# SCH_single-layer-routed_2024-06-21.net
KiCad netlist of a schematic drawn in EasyEDA
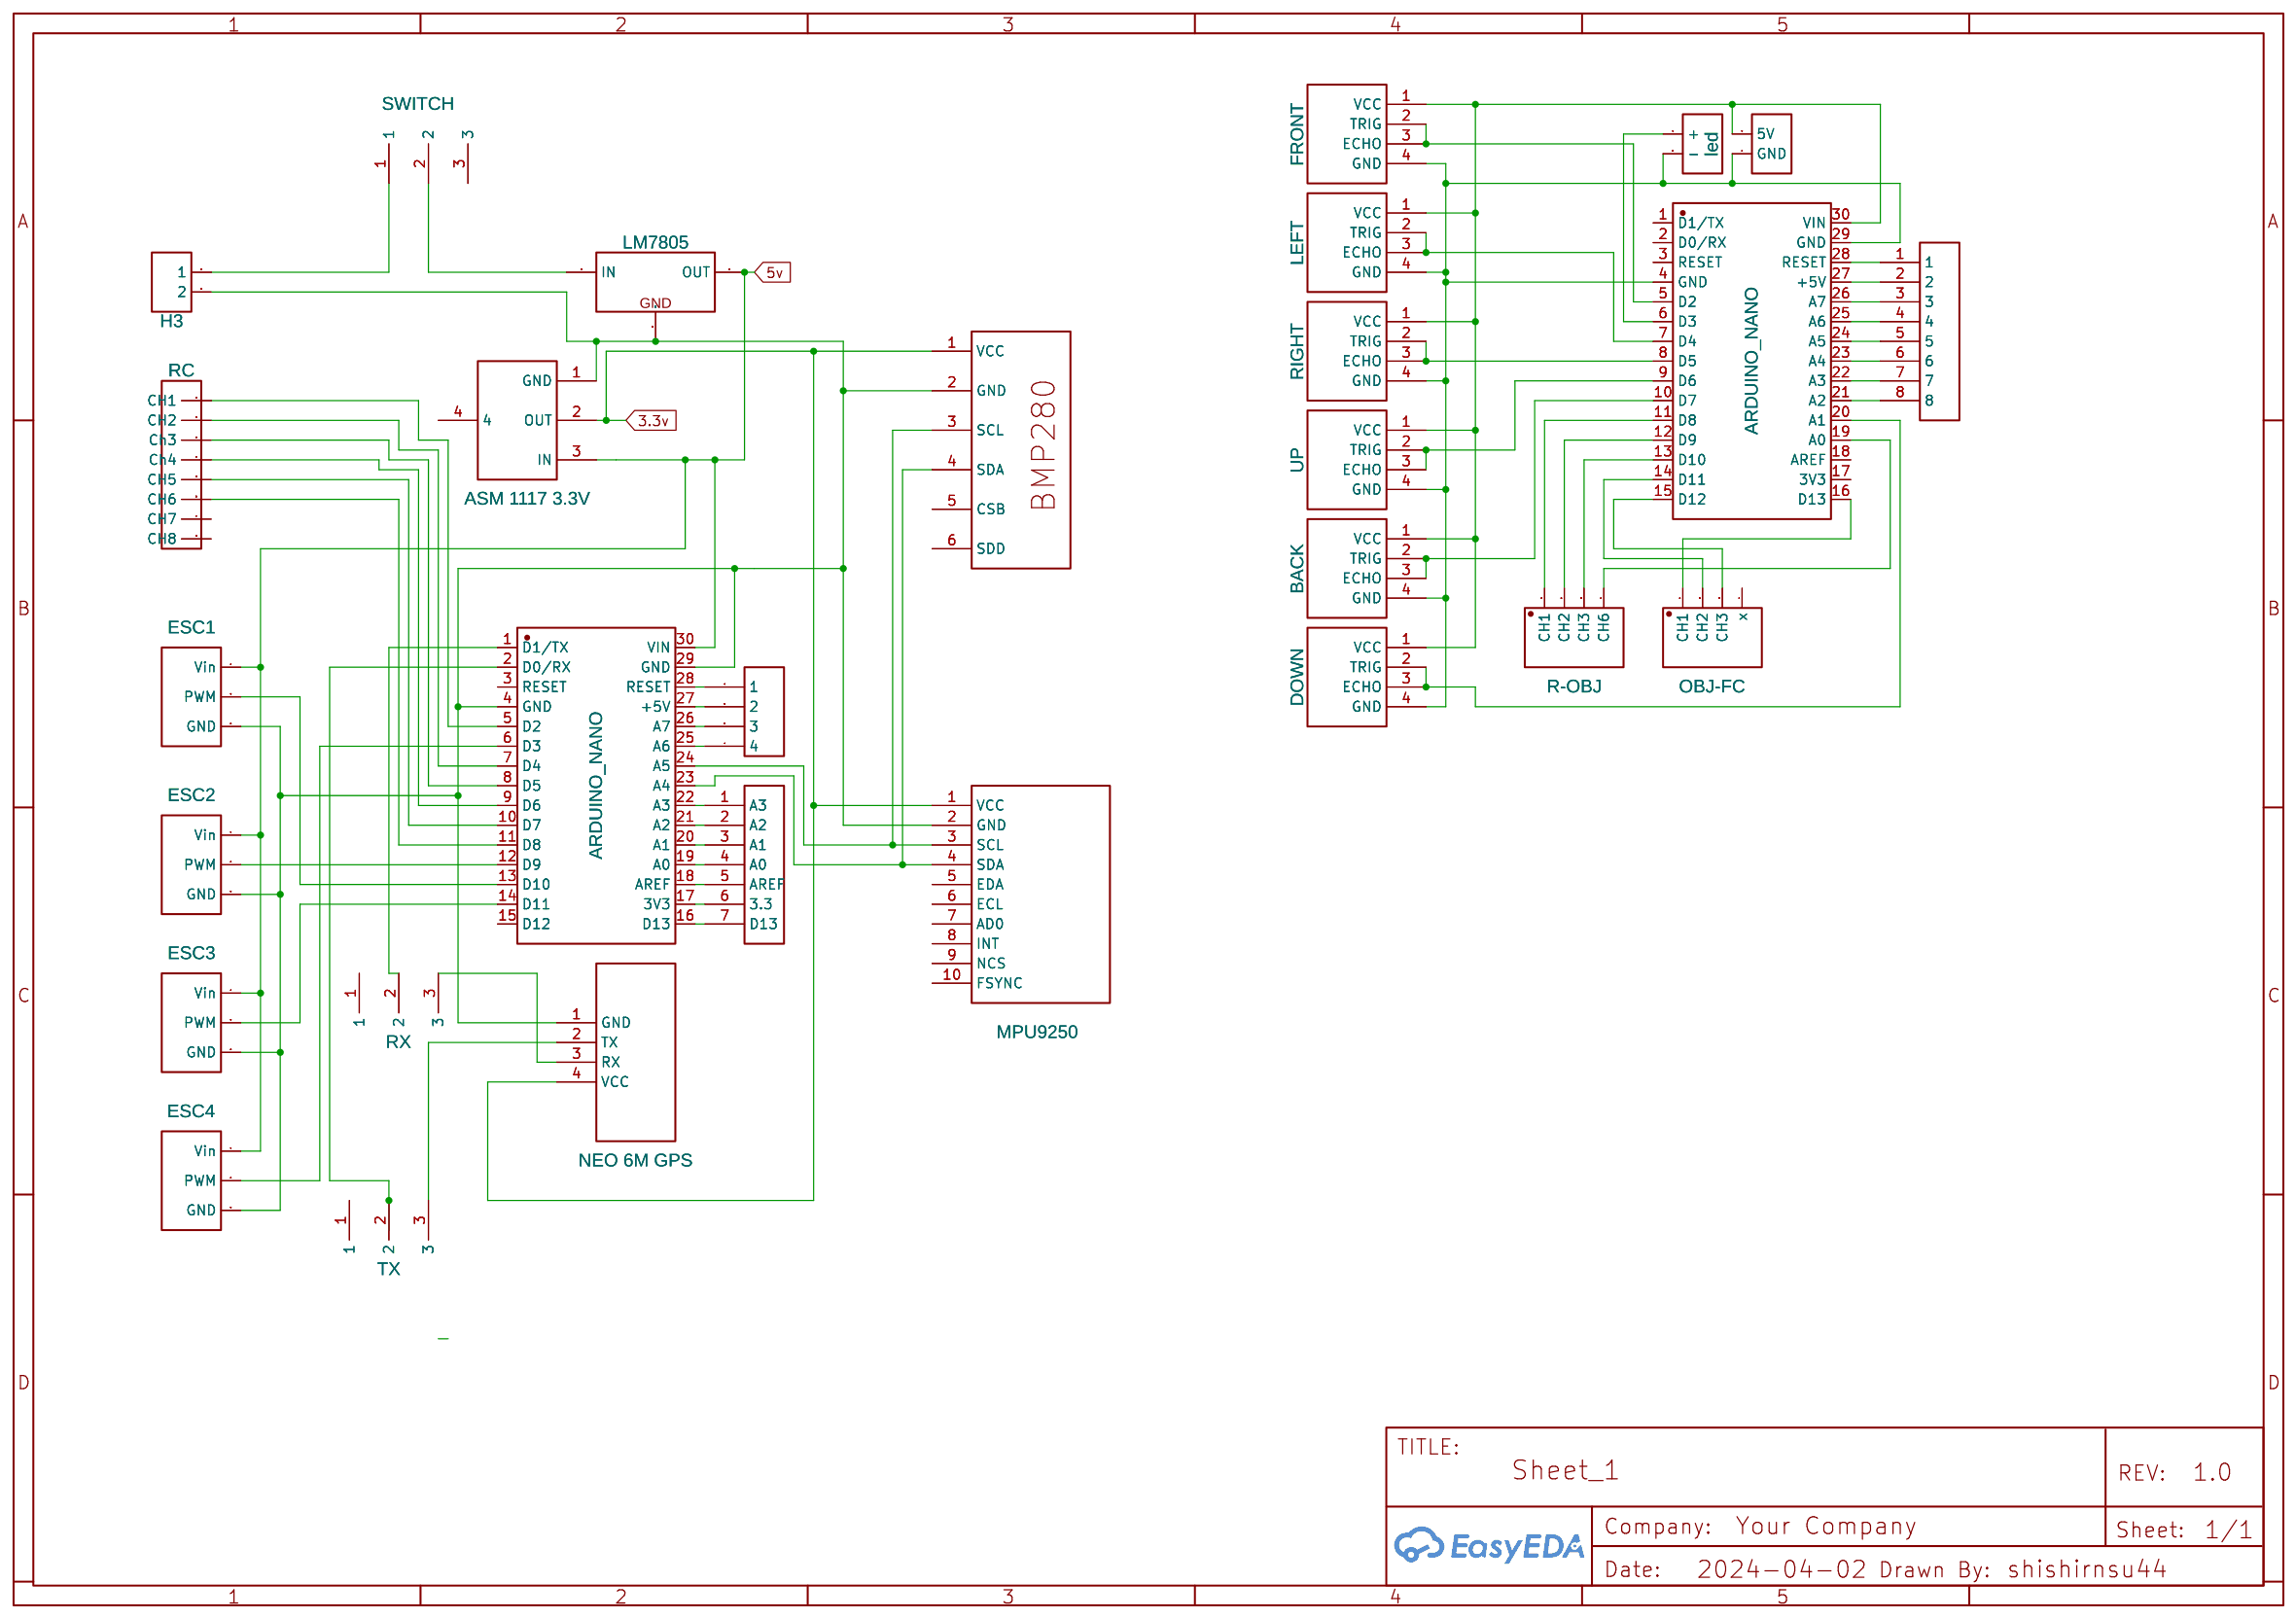
[diagram p0: schematic sheet]

(export (version "E")
  (design (tool "Eeschema 10.0.6"))
  (components
    (comp (ref "BACK")
      (value "BORNERA SENSOR ULTRASONICO HC-SR04")
      (libsource (lib "") (part "BORNERA SENSOR ULTRASONICO HC-SR04"))
    )
    (comp (ref "DOWN") (value "Down") (libsource (lib "") (part "BORNERA SENSOR ULTRASONICO HC-SR04_5")))
    (comp (ref "ESC1") (value "ESC") (libsource (lib "") (part "ESC")))
    (comp (ref "ESC2") (value "ESC") (libsource (lib "") (part "ESC")))
    (comp (ref "ESC3") (value "ESC") (libsource (lib "") (part "ESC")))
    (comp (ref "ESC4") (value "ESC") (libsource (lib "") (part "ESC")))
    (comp (ref "FRONT") (value "Front") (libsource (lib "") (part "BORNERA SENSOR ULTRASONICO HC-SR04_2")))
    (comp (ref "H1")
      (value "1x2_Male_Pin_Header")
      (fields (field (name "Manufacturer Part") "210S-1*8P L=11.6MMGold-plated black"))
      (libsource (lib "") (part "1x2_Male_Pin_Header_2"))
    )
    (comp (ref "H2")
      (value "led")
      (fields (field (name "Manufacturer Part") "210S-1*8P L=11.6MMGold-plated black"))
      (libsource (lib "") (part "1x2_Male_Pin_Header"))
    )
    (comp (ref "H3")
      (value "1x2_Male_Pin_Header")
      (fields (field (name "Manufacturer Part") "210S-1*8P L=11.6MMGold-plated black"))
      (libsource (lib "") (part "1x2_Male_Pin_Header_1"))
    )
    (comp (ref "LEFT") (value "Left") (libsource (lib "") (part "BORNERA SENSOR ULTRASONICO HC-SR04_4")))
    (comp (ref "MODULE2")
      (value "NEO 6M GPS")
      (libsource (lib "") (part "UBLOX NEO 6M GPS MODULE NO-ANTENNA"))
    )
    (comp (ref "OBJ-FC")
      (value "Header-Male-2.54_1x4")
      (fields (field (name "Manufacturer Part") "B-2100S04P-A110") (field (name "Manufacturer") "Ckmtw(灿科盟)"))
      (libsource (lib "") (part "Header-Male-2.54_1x4_1"))
    )
    (comp (ref "P2")
      (value "HEADER4x1")
      (fields (field (name "Manufacturer Part") "New SchematicLib"))
      (libsource (lib "") (part "HEADER4x1"))
    )
    (comp (ref "R-OBJ")
      (value "Header-Male-2.54_1x4")
      (fields (field (name "Manufacturer Part") "B-2100S04P-A110") (field (name "Manufacturer") "Ckmtw(灿科盟)"))
      (libsource (lib "") (part "Header-Male-2.54_1x4"))
    )
    (comp (ref "RC")
      (value "pinheader08x1")
      (fields (field (name "Manufacturer Part") "Header 6x1"))
      (libsource (lib "") (part "pinheader08x1"))
    )
    (comp (ref "RIGHT") (value "Rignt") (libsource (lib "") (part "BORNERA SENSOR ULTRASONICO HC-SR04_3")))
    (comp (ref "RX") (value "SlideSwitch") (libsource (lib "") (part "SlideSwitch_2")))
    (comp (ref "SWITCH") (value "SlideSwitch") (libsource (lib "") (part "SlideSwitch")))
    (comp (ref "TX") (value "SlideSwitch") (libsource (lib "") (part "SlideSwitch_1")))
    (comp (ref "U1") (value "ARDUINO_NANO") (libsource (lib "") (part "ARDUINO_NANO")))
    (comp (ref "U2")
      (value "BMP280 Pressure/Temp/Altitudesensor")
      (libsource (lib "") (part "BMP280 Pressure/Temp/Altitudesensor"))
    )
    (comp (ref "U3") (value "MPU9250") (libsource (lib "") (part "GY9250(MPU9250)")))
    (comp (ref "U4")
      (value "LM7805")
      (fields (field (name "Manufacturer") "TF"))
      (libsource (lib "") (part "LM7805"))
    )
    (comp (ref "U5") (value "ASM 1117 3.3V") (libsource (lib "") (part "ASM 1117 5.0V")))
    (comp (ref "U6") (value "ARDUINO_NANO") (libsource (lib "") (part "ARDUINO_NANO")))
    (comp (ref "U7") (value "header8x1") (libsource (lib "") (part "header8x1")))
    (comp (ref "U9") (value "header7X1") (libsource (lib "") (part "header7X1")))
    (comp (ref "UP")
      (value "BORNERA SENSOR ULTRASONICO HC-SR04")
      (libsource (lib "") (part "BORNERA SENSOR ULTRASONICO HC-SR04_1"))
    )
  )
  (nets
    (net (code "1") (name "3.3v") (class "Default")
      (node (ref "MODULE2") (pin "4") (pinfunction "VCC_4") (pintype "unspecified"))
      (node (ref "U2") (pin "1") (pinfunction "VCC_1") (pintype "unspecified"))
      (node (ref "U3") (pin "1") (pinfunction "VCC_1") (pintype "unspecified"))
      (node (ref "U5") (pin "2") (pinfunction "OUT_2") (pintype "unspecified"))
    )
    (net (code "2") (name "5v") (class "Default")
      (node (ref "ESC1") (pin "1") (pinfunction "Vin_1") (pintype "input"))
      (node (ref "ESC2") (pin "1") (pinfunction "Vin_1") (pintype "input"))
      (node (ref "ESC3") (pin "1") (pinfunction "Vin_1") (pintype "input"))
      (node (ref "ESC4") (pin "1") (pinfunction "Vin_1") (pintype "input"))
      (node (ref "U1") (pin "30") (pinfunction "VIN_30") (pintype "unspecified"))
      (node (ref "U4") (pin "3") (pinfunction "OUT_3") (pintype "unspecified"))
      (node (ref "U5") (pin "3") (pinfunction "IN_3") (pintype "unspecified"))
    )
    (net (code "3") (name "Net-(BACK-ECHO)") (class "Default")
      (node (ref "BACK") (pin "2") (pinfunction "TRIG_2") (pintype "unspecified"))
      (node (ref "BACK") (pin "3") (pinfunction "ECHO_3") (pintype "unspecified"))
      (node (ref "U6") (pin "10") (pinfunction "D7_10") (pintype "unspecified"))
    )
    (net (code "4") (name "Net-(BACK-GND)") (class "Default")
      (node (ref "BACK") (pin "4") (pinfunction "GND_4") (pintype "unspecified"))
      (node (ref "DOWN") (pin "4") (pinfunction "GND_4") (pintype "unspecified"))
      (node (ref "FRONT") (pin "4") (pinfunction "GND_4") (pintype "unspecified"))
      (node (ref "H1") (pin "1") (pinfunction "GND_1") (pintype "unspecified"))
      (node (ref "H2") (pin "2") (pinfunction "-_2") (pintype "unspecified"))
      (node (ref "LEFT") (pin "4") (pinfunction "GND_4") (pintype "unspecified"))
      (node (ref "RIGHT") (pin "4") (pinfunction "GND_4") (pintype "unspecified"))
      (node (ref "U6") (pin "29") (pinfunction "GND_29") (pintype "unspecified"))
      (node (ref "U6") (pin "4") (pinfunction "GND_4") (pintype "unspecified"))
      (node (ref "UP") (pin "4") (pinfunction "GND_4") (pintype "unspecified"))
    )
    (net (code "5") (name "Net-(BACK-VCC)") (class "Default")
      (node (ref "BACK") (pin "1") (pinfunction "VCC_1") (pintype "unspecified"))
      (node (ref "DOWN") (pin "1") (pinfunction "VCC_1") (pintype "unspecified"))
      (node (ref "FRONT") (pin "1") (pinfunction "VCC_1") (pintype "unspecified"))
      (node (ref "H1") (pin "2") (pinfunction "5V_2") (pintype "unspecified"))
      (node (ref "LEFT") (pin "1") (pinfunction "VCC_1") (pintype "unspecified"))
      (node (ref "RIGHT") (pin "1") (pinfunction "VCC_1") (pintype "unspecified"))
      (node (ref "U6") (pin "30") (pinfunction "VIN_30") (pintype "unspecified"))
      (node (ref "UP") (pin "1") (pinfunction "VCC_1") (pintype "unspecified"))
    )
    (net (code "6") (name "Net-(DOWN-ECHO)") (class "Default")
      (node (ref "DOWN") (pin "2") (pinfunction "TRIG_2") (pintype "unspecified"))
      (node (ref "DOWN") (pin "3") (pinfunction "ECHO_3") (pintype "unspecified"))
      (node (ref "U6") (pin "20") (pinfunction "A1_20") (pintype "unspecified"))
    )
    (net (code "7") (name "Net-(ESC1-GND)") (class "Default")
      (node (ref "ESC1") (pin "3") (pinfunction "GND_3") (pintype "input"))
      (node (ref "ESC2") (pin "3") (pinfunction "GND_3") (pintype "input"))
      (node (ref "ESC3") (pin "3") (pinfunction "GND_3") (pintype "input"))
      (node (ref "ESC4") (pin "3") (pinfunction "GND_3") (pintype "input"))
      (node (ref "H3") (pin "2") (pinfunction "2_2") (pintype "unspecified"))
      (node (ref "MODULE2") (pin "1") (pinfunction "GND_1") (pintype "unspecified"))
      (node (ref "U1") (pin "29") (pinfunction "GND_29") (pintype "unspecified"))
      (node (ref "U1") (pin "4") (pinfunction "GND_4") (pintype "unspecified"))
      (node (ref "U2") (pin "2") (pinfunction "GND_2") (pintype "unspecified"))
      (node (ref "U3") (pin "2") (pinfunction "GND_2") (pintype "unspecified"))
      (node (ref "U4") (pin "2") (pinfunction "GND_2") (pintype "unspecified"))
      (node (ref "U5") (pin "1") (pinfunction "GND_1") (pintype "unspecified"))
    )
    (net (code "8") (name "Net-(ESC1-PWM)") (class "Default")
      (node (ref "ESC1") (pin "2") (pinfunction "PWM_2") (pintype "input"))
      (node (ref "U1") (pin "13") (pinfunction "D10_13") (pintype "unspecified"))
    )
    (net (code "9") (name "Net-(ESC2-PWM)") (class "Default")
      (node (ref "ESC2") (pin "2") (pinfunction "PWM_2") (pintype "input"))
      (node (ref "U1") (pin "12") (pinfunction "D9_12") (pintype "unspecified"))
    )
    (net (code "10") (name "Net-(ESC3-PWM)") (class "Default")
      (node (ref "ESC3") (pin "2") (pinfunction "PWM_2") (pintype "input"))
      (node (ref "U1") (pin "14") (pinfunction "D11_14") (pintype "unspecified"))
    )
    (net (code "11") (name "Net-(ESC4-PWM)") (class "Default")
      (node (ref "ESC4") (pin "2") (pinfunction "PWM_2") (pintype "input"))
      (node (ref "U1") (pin "6") (pinfunction "D3_6") (pintype "unspecified"))
    )
    (net (code "12") (name "Net-(FRONT-ECHO)") (class "Default")
      (node (ref "FRONT") (pin "2") (pinfunction "TRIG_2") (pintype "unspecified"))
      (node (ref "FRONT") (pin "3") (pinfunction "ECHO_3") (pintype "unspecified"))
      (node (ref "U6") (pin "5") (pinfunction "D2_5") (pintype "unspecified"))
    )
    (net (code "13") (name "Net-(H2-+)") (class "Default")
      (node (ref "H2") (pin "1") (pinfunction "+_1") (pintype "unspecified"))
      (node (ref "U6") (pin "6") (pinfunction "D3_6") (pintype "unspecified"))
    )
    (net (code "14") (name "Net-(H3-Pad1)") (class "Default")
      (node (ref "H3") (pin "1") (pinfunction "1_1") (pintype "unspecified"))
      (node (ref "SWITCH") (pin "1") (pinfunction "1_1") (pintype "unspecified"))
    )
    (net (code "15") (name "Net-(LEFT-ECHO)") (class "Default")
      (node (ref "LEFT") (pin "2") (pinfunction "TRIG_2") (pintype "unspecified"))
      (node (ref "LEFT") (pin "3") (pinfunction "ECHO_3") (pintype "unspecified"))
      (node (ref "U6") (pin "7") (pinfunction "D4_7") (pintype "unspecified"))
    )
    (net (code "16") (name "Net-(MODULE2-RX)") (class "Default")
      (node (ref "MODULE2") (pin "3") (pinfunction "RX_3") (pintype "unspecified"))
      (node (ref "RX") (pin "3") (pinfunction "3_3") (pintype "unspecified"))
    )
    (net (code "17") (name "Net-(MODULE2-TX)") (class "Default")
      (node (ref "MODULE2") (pin "2") (pinfunction "TX_2") (pintype "unspecified"))
      (node (ref "TX") (pin "3") (pinfunction "3_3") (pintype "unspecified"))
    )
    (net (code "18") (name "Net-(OBJ-FC-CH1)") (class "Default")
      (node (ref "OBJ-FC") (pin "1") (pinfunction "CH1_1") (pintype "unspecified"))
      (node (ref "U6") (pin "16") (pinfunction "D13_16") (pintype "unspecified"))
    )
    (net (code "19") (name "Net-(OBJ-FC-CH2)") (class "Default")
      (node (ref "OBJ-FC") (pin "2") (pinfunction "CH2_2") (pintype "unspecified"))
      (node (ref "U6") (pin "14") (pinfunction "D11_14") (pintype "unspecified"))
    )
    (net (code "20") (name "Net-(OBJ-FC-CH3)") (class "Default")
      (node (ref "OBJ-FC") (pin "3") (pinfunction "CH3_3") (pintype "unspecified"))
      (node (ref "U6") (pin "15") (pinfunction "D12_15") (pintype "unspecified"))
    )
    (net (code "21") (name "Net-(P2-Pad1)") (class "Default")
      (node (ref "P2") (pin "1") (pinfunction "1_1") (pintype "input"))
      (node (ref "U1") (pin "28") (pinfunction "RESET_28") (pintype "unspecified"))
    )
    (net (code "22") (name "Net-(R-OBJ-CH1)") (class "Default")
      (node (ref "R-OBJ") (pin "1") (pinfunction "CH1_1") (pintype "unspecified"))
      (node (ref "U6") (pin "11") (pinfunction "D8_11") (pintype "unspecified"))
    )
    (net (code "23") (name "Net-(R-OBJ-CH2)") (class "Default")
      (node (ref "R-OBJ") (pin "2") (pinfunction "CH2_2") (pintype "unspecified"))
      (node (ref "U6") (pin "12") (pinfunction "D9_12") (pintype "unspecified"))
    )
    (net (code "24") (name "Net-(R-OBJ-CH3)") (class "Default")
      (node (ref "R-OBJ") (pin "3") (pinfunction "CH3_3") (pintype "unspecified"))
      (node (ref "U6") (pin "13") (pinfunction "D10_13") (pintype "unspecified"))
    )
    (net (code "25") (name "Net-(R-OBJ-CH6)") (class "Default")
      (node (ref "R-OBJ") (pin "4") (pinfunction "CH6_4") (pintype "unspecified"))
      (node (ref "U6") (pin "19") (pinfunction "A0_19") (pintype "unspecified"))
    )
    (net (code "26") (name "Net-(RC-CH1)") (class "Default")
      (node (ref "RC") (pin "1") (pinfunction "CH1_1") (pintype "unspecified"))
      (node (ref "U1") (pin "5") (pinfunction "D2_5") (pintype "unspecified"))
    )
    (net (code "27") (name "Net-(RC-CH2)") (class "Default")
      (node (ref "RC") (pin "2") (pinfunction "CH2_2") (pintype "unspecified"))
      (node (ref "U1") (pin "7") (pinfunction "D4_7") (pintype "unspecified"))
    )
    (net (code "28") (name "Net-(RC-CH5)") (class "Default")
      (node (ref "RC") (pin "5") (pinfunction "CH5_5") (pintype "unspecified"))
      (node (ref "U1") (pin "10") (pinfunction "D7_10") (pintype "unspecified"))
    )
    (net (code "29") (name "Net-(RC-CH6)") (class "Default")
      (node (ref "RC") (pin "6") (pinfunction "CH6_6") (pintype "unspecified"))
      (node (ref "U1") (pin "11") (pinfunction "D8_11") (pintype "unspecified"))
    )
    (net (code "30") (name "Net-(RC-Ch3)") (class "Default")
      (node (ref "RC") (pin "3") (pinfunction "Ch3_3") (pintype "unspecified"))
      (node (ref "U1") (pin "8") (pinfunction "D5_8") (pintype "unspecified"))
    )
    (net (code "31") (name "Net-(RC-Ch4)") (class "Default")
      (node (ref "RC") (pin "4") (pinfunction "Ch4_4") (pintype "unspecified"))
      (node (ref "U1") (pin "9") (pinfunction "D6_9") (pintype "unspecified"))
    )
    (net (code "32") (name "Net-(RIGHT-ECHO)") (class "Default")
      (node (ref "RIGHT") (pin "2") (pinfunction "TRIG_2") (pintype "unspecified"))
      (node (ref "RIGHT") (pin "3") (pinfunction "ECHO_3") (pintype "unspecified"))
      (node (ref "U6") (pin "8") (pinfunction "D5_8") (pintype "unspecified"))
    )
    (net (code "33") (name "Net-(U1-+5V)") (class "Default")
      (node (ref "P2") (pin "2") (pinfunction "2_2") (pintype "input"))
      (node (ref "U1") (pin "27") (pinfunction "+5V_27") (pintype "unspecified"))
    )
    (net (code "34") (name "Net-(U1-3V3)") (class "Default")
      (node (ref "U1") (pin "17") (pinfunction "3V3_17") (pintype "unspecified"))
      (node (ref "U9") (pin "6") (pinfunction "3.3_6") (pintype "unspecified"))
    )
    (net (code "35") (name "Net-(U1-A0)") (class "Default")
      (node (ref "U1") (pin "19") (pinfunction "A0_19") (pintype "unspecified"))
      (node (ref "U9") (pin "4") (pinfunction "A0_4") (pintype "unspecified"))
    )
    (net (code "36") (name "Net-(U1-A1)") (class "Default")
      (node (ref "U1") (pin "20") (pinfunction "A1_20") (pintype "unspecified"))
      (node (ref "U9") (pin "3") (pinfunction "A1_3") (pintype "unspecified"))
    )
    (net (code "37") (name "Net-(U1-A2)") (class "Default")
      (node (ref "U1") (pin "21") (pinfunction "A2_21") (pintype "unspecified"))
      (node (ref "U9") (pin "2") (pinfunction "A2_2") (pintype "unspecified"))
    )
    (net (code "38") (name "Net-(U1-A3)") (class "Default")
      (node (ref "U1") (pin "22") (pinfunction "A3_22") (pintype "unspecified"))
      (node (ref "U9") (pin "1") (pinfunction "A3_1") (pintype "unspecified"))
    )
    (net (code "39") (name "Net-(U1-A4)") (class "Default")
      (node (ref "U1") (pin "23") (pinfunction "A4_23") (pintype "unspecified"))
      (node (ref "U2") (pin "4") (pinfunction "SDA_4") (pintype "unspecified"))
      (node (ref "U3") (pin "4") (pinfunction "SDA_4") (pintype "unspecified"))
    )
    (net (code "40") (name "Net-(U1-A5)") (class "Default")
      (node (ref "U1") (pin "24") (pinfunction "A5_24") (pintype "unspecified"))
      (node (ref "U2") (pin "3") (pinfunction "SCL_3") (pintype "unspecified"))
      (node (ref "U3") (pin "3") (pinfunction "SCL_3") (pintype "unspecified"))
    )
    (net (code "41") (name "Net-(U1-A6)") (class "Default")
      (node (ref "P2") (pin "4") (pinfunction "4_4") (pintype "input"))
      (node (ref "U1") (pin "25") (pinfunction "A6_25") (pintype "unspecified"))
    )
    (net (code "42") (name "Net-(U1-A7)") (class "Default")
      (node (ref "P2") (pin "3") (pinfunction "3_3") (pintype "input"))
      (node (ref "U1") (pin "26") (pinfunction "A7_26") (pintype "unspecified"))
    )
    (net (code "43") (name "Net-(U1-AREF)") (class "Default")
      (node (ref "U1") (pin "18") (pinfunction "AREF_18") (pintype "unspecified"))
      (node (ref "U9") (pin "5") (pinfunction "AREF_5") (pintype "unspecified"))
    )
    (net (code "44") (name "Net-(U1-D0{slash}RX)") (class "Default")
      (node (ref "TX") (pin "2") (pinfunction "2_2") (pintype "unspecified"))
      (node (ref "U1") (pin "2") (pinfunction "D0/RX_2") (pintype "unspecified"))
    )
    (net (code "45") (name "Net-(U1-D1{slash}TX)") (class "Default")
      (node (ref "RX") (pin "2") (pinfunction "2_2") (pintype "unspecified"))
      (node (ref "U1") (pin "1") (pinfunction "D1/TX_1") (pintype "unspecified"))
    )
    (net (code "46") (name "Net-(U1-D13)") (class "Default")
      (node (ref "U1") (pin "16") (pinfunction "D13_16") (pintype "unspecified"))
      (node (ref "U9") (pin "7") (pinfunction "D13_7") (pintype "unspecified"))
    )
    (net (code "47") (name "Net-(U4-IN)") (class "Default")
      (node (ref "SWITCH") (pin "2") (pinfunction "2_2") (pintype "unspecified"))
      (node (ref "U4") (pin "1") (pinfunction "IN_1") (pintype "unspecified"))
    )
    (net (code "48") (name "Net-(U6-+5V)") (class "Default")
      (node (ref "U6") (pin "27") (pinfunction "+5V_27") (pintype "unspecified"))
      (node (ref "U7") (pin "2") (pinfunction "2_2") (pintype "unspecified"))
    )
    (net (code "49") (name "Net-(U6-A2)") (class "Default")
      (node (ref "U6") (pin "21") (pinfunction "A2_21") (pintype "unspecified"))
      (node (ref "U7") (pin "8") (pinfunction "8_8") (pintype "unspecified"))
    )
    (net (code "50") (name "Net-(U6-A3)") (class "Default")
      (node (ref "U6") (pin "22") (pinfunction "A3_22") (pintype "unspecified"))
      (node (ref "U7") (pin "7") (pinfunction "7_7") (pintype "unspecified"))
    )
    (net (code "51") (name "Net-(U6-A4)") (class "Default")
      (node (ref "U6") (pin "23") (pinfunction "A4_23") (pintype "unspecified"))
      (node (ref "U7") (pin "6") (pinfunction "6_6") (pintype "unspecified"))
    )
    (net (code "52") (name "Net-(U6-A5)") (class "Default")
      (node (ref "U6") (pin "24") (pinfunction "A5_24") (pintype "unspecified"))
      (node (ref "U7") (pin "5") (pinfunction "5_5") (pintype "unspecified"))
    )
    (net (code "53") (name "Net-(U6-A6)") (class "Default")
      (node (ref "U6") (pin "25") (pinfunction "A6_25") (pintype "unspecified"))
      (node (ref "U7") (pin "4") (pinfunction "4_4") (pintype "unspecified"))
    )
    (net (code "54") (name "Net-(U6-A7)") (class "Default")
      (node (ref "U6") (pin "26") (pinfunction "A7_26") (pintype "unspecified"))
      (node (ref "U7") (pin "3") (pinfunction "3_3") (pintype "unspecified"))
    )
    (net (code "55") (name "Net-(U6-D6)") (class "Default")
      (node (ref "U6") (pin "9") (pinfunction "D6_9") (pintype "unspecified"))
      (node (ref "UP") (pin "2") (pinfunction "TRIG_2") (pintype "unspecified"))
      (node (ref "UP") (pin "3") (pinfunction "ECHO_3") (pintype "unspecified"))
    )
    (net (code "56") (name "Net-(U6-RESET-Pad28)") (class "Default")
      (node (ref "U6") (pin "28") (pinfunction "RESET_28") (pintype "unspecified"))
      (node (ref "U7") (pin "1") (pinfunction "1_1") (pintype "unspecified"))
    )
    (net (code "57") (name "unconnected-(OBJ-FC-x-Pad4)") (class "Default")
      (node (ref "OBJ-FC") (pin "4") (pinfunction "x_4") (pintype "unspecified"))
    )
    (net (code "58") (name "unconnected-(RC-CH7-Pad7)") (class "Default")
      (node (ref "RC") (pin "7") (pinfunction "CH7_7") (pintype "unspecified"))
    )
    (net (code "59") (name "unconnected-(RC-CH8-Pad8)") (class "Default")
      (node (ref "RC") (pin "8") (pinfunction "CH8_8") (pintype "unspecified"))
    )
    (net (code "60") (name "unconnected-(RX-Pad1)") (class "Default")
      (node (ref "RX") (pin "1") (pinfunction "1_1") (pintype "unspecified"))
    )
    (net (code "61") (name "unconnected-(SWITCH-Pad3)") (class "Default")
      (node (ref "SWITCH") (pin "3") (pinfunction "3_3") (pintype "unspecified"))
    )
    (net (code "62") (name "unconnected-(TX-Pad1)") (class "Default")
      (node (ref "TX") (pin "1") (pinfunction "1_1") (pintype "unspecified"))
    )
    (net (code "63") (name "unconnected-(U1-D12-Pad15)") (class "Default")
      (node (ref "U1") (pin "15") (pinfunction "D12_15") (pintype "unspecified"))
    )
    (net (code "64") (name "unconnected-(U1-RESET-Pad3)") (class "Default")
      (node (ref "U1") (pin "3") (pinfunction "RESET_3") (pintype "unspecified"))
    )
    (net (code "65") (name "unconnected-(U2-CSB-Pad5)") (class "Default")
      (node (ref "U2") (pin "5") (pinfunction "CSB_5") (pintype "unspecified"))
    )
    (net (code "66") (name "unconnected-(U2-SDD-Pad6)") (class "Default")
      (node (ref "U2") (pin "6") (pinfunction "SDD_6") (pintype "unspecified"))
    )
    (net (code "67") (name "unconnected-(U3-AD0-Pad7)") (class "Default")
      (node (ref "U3") (pin "7") (pinfunction "AD0_7") (pintype "unspecified"))
    )
    (net (code "68") (name "unconnected-(U3-ECL-Pad6)") (class "Default")
      (node (ref "U3") (pin "6") (pinfunction "ECL_6") (pintype "unspecified"))
    )
    (net (code "69") (name "unconnected-(U3-EDA-Pad5)") (class "Default")
      (node (ref "U3") (pin "5") (pinfunction "EDA_5") (pintype "unspecified"))
    )
    (net (code "70") (name "unconnected-(U3-FSYNC-Pad10)") (class "Default")
      (node (ref "U3") (pin "10") (pinfunction "FSYNC_10") (pintype "unspecified"))
    )
    (net (code "71") (name "unconnected-(U3-INT-Pad8)") (class "Default")
      (node (ref "U3") (pin "8") (pinfunction "INT_8") (pintype "unspecified"))
    )
    (net (code "72") (name "unconnected-(U3-NCS-Pad9)") (class "Default")
      (node (ref "U3") (pin "9") (pinfunction "NCS_9") (pintype "unspecified"))
    )
    (net (code "73") (name "unconnected-(U5-Pad4)") (class "Default")
      (node (ref "U5") (pin "4") (pinfunction "4_4") (pintype "unspecified"))
    )
    (net (code "74") (name "unconnected-(U6-3V3-Pad17)") (class "Default")
      (node (ref "U6") (pin "17") (pinfunction "3V3_17") (pintype "unspecified"))
    )
    (net (code "75") (name "unconnected-(U6-AREF-Pad18)") (class "Default")
      (node (ref "U6") (pin "18") (pinfunction "AREF_18") (pintype "unspecified"))
    )
    (net (code "76") (name "unconnected-(U6-D0{slash}RX-Pad2)") (class "Default")
      (node (ref "U6") (pin "2") (pinfunction "D0/RX_2") (pintype "unspecified"))
    )
    (net (code "77") (name "unconnected-(U6-D1{slash}TX-Pad1)") (class "Default")
      (node (ref "U6") (pin "1") (pinfunction "D1/TX_1") (pintype "unspecified"))
    )
    (net (code "78") (name "unconnected-(U6-RESET-Pad3)") (class "Default")
      (node (ref "U6") (pin "3") (pinfunction "RESET_3") (pintype "unspecified"))
    )
  )
)
